# Cell.net
KiCad netlist of a schematic drawn in Altium Designer
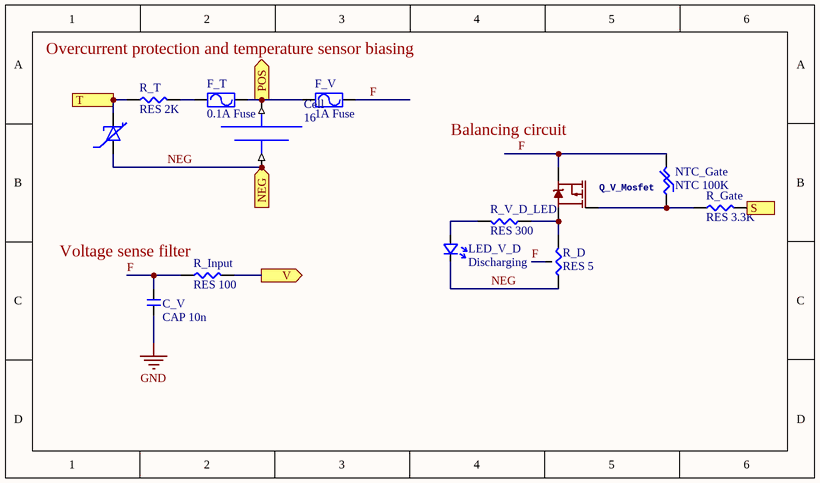
[diagram p0: Cell.SchDoc]

(export (version "E")
  (design (tool "Eeschema 10.0.6"))
  (components
    (comp (ref "Cell")
      (value "16")
      (footprint "Li1x7pVTC6T_Clips")
      (libsource (lib "ife18_TS_BMS_LTC6813_v2_Library") (part "Li1x7pVTC6T_Clip"))
    )
    (comp (ref "C_V")
      (value "CAP 10n")
      (footprint "CAP-0603")
      (description "CAP-0603")
      (libsource (lib "altium-import") (part "root_1_CAP-0603_"))
    )
    (comp (ref "F_T")
      (value "0.1A Fuse")
      (footprint "2410SMD")
      (description "0679L")
      (libsource (lib "altium-import") (part "root_0_0679L_"))
    )
    (comp (ref "F_V")
      (value "1A Fuse")
      (footprint "2410SMD")
      (description "0679L")
      (libsource (lib "altium-import") (part "root_0_0679L_"))
    )
    (comp (ref "LED_V_D")
      (value "Discharging")
      (footprint "LED-0603")
      (description "LED-0603")
      (libsource (lib "altium-import") (part "root_3_LED-0603_"))
    )
    (comp (ref "NTC_Gate")
      (value "NTC 100K")
      (footprint "NTC-0603")
      (description "NTC-0603")
      (libsource (lib "altium-import") (part "root_1_NTC-0603_"))
    )
    (comp (ref "Q_V_Mosfet")
      (value "~")
      (footprint "TO252")
      (description "DMP10H400SK3-13")
      (libsource (lib "altium-import") (part "root_0_DMP10H400SK3-13_"))
    )
    (comp (ref "R_D")
      (value "RES 5")
      (footprint "TO252-TKH-45")
      (description "TKH45")
      (libsource (lib "altium-import") (part "root_1_TKH45_"))
    )
    (comp (ref "R_Gate")
      (value "RES 3.3K")
      (footprint "RES-0603")
      (libsource (lib "altium-import") (part "root_0_RES-0603_"))
    )
    (comp (ref "R_Input")
      (value "RES 100")
      (footprint "RES-0603")
      (libsource (lib "altium-import") (part "root_0_RES-0603_"))
    )
    (comp (ref "R_T")
      (value "RES 2K")
      (footprint "RES-0603")
      (libsource (lib "altium-import") (part "root_0_RES-0603_"))
    )
    (comp (ref "R_V_D_LED")
      (value "RES 300")
      (footprint "RES-0603")
      (libsource (lib "altium-import") (part "root_2_RES-0603_"))
    )
  )
  (nets
    (net (code "1") (name "/F") (class "Default")
      (node (ref "C_V") (pin "2") (pinfunction "2_2") (pintype "passive"))
      (node (ref "F_V") (pin "1") (pinfunction "1_1") (pintype "passive"))
      (node (ref "NTC_Gate") (pin "2") (pinfunction "2_2") (pintype "passive"))
      (node (ref "Q_V_Mosfet") (pin "3") (pinfunction "S_3") (pintype "passive"))
      (node (ref "R_D") (pin "3") (pinfunction "3_3") (pintype "passive"))
      (node (ref "R_Input") (pin "1") (pinfunction "1_1") (pintype "passive"))
    )
    (net (code "2") (name "/NEG") (class "Default")
      (node (ref "Cell") (pin "-") (pinfunction "-_-") (pintype "input"))
      (node (ref "Cell") (pin "-L") (pinfunction "-L_-L") (pintype "passive"))
      (node (ref "Cell") (pin "-O") (pinfunction "-O_-O") (pintype "passive"))
      (node (ref "Cell") (pin "-R") (pinfunction "-R_-R") (pintype "passive"))
      (node (ref "Cell") (pin "T-") (pinfunction "T-_T-") (pintype "passive"))
      (node (ref "LED_V_D") (pin "K") (pinfunction "K_K") (pintype "passive"))
      (node (ref "R_D") (pin "1") (pinfunction "1_1") (pintype "passive"))
    )
    (net (code "3") (name "/POS") (class "Default")
      (node (ref "Cell") (pin "+") (pinfunction "+_+") (pintype "output"))
      (node (ref "Cell") (pin "+L") (pinfunction "+L_+L") (pintype "passive"))
      (node (ref "Cell") (pin "+O") (pinfunction "+O_+O") (pintype "passive"))
      (node (ref "Cell") (pin "+R") (pinfunction "+R_+R") (pintype "passive"))
      (node (ref "F_T") (pin "1") (pinfunction "1_1") (pintype "passive"))
      (node (ref "F_V") (pin "2") (pinfunction "2_2") (pintype "passive"))
    )
    (net (code "4") (name "/S") (class "Default")
      (node (ref "R_Gate") (pin "2") (pinfunction "2_2") (pintype "passive"))
    )
    (net (code "5") (name "/T") (class "Default")
      (node (ref "Cell") (pin "T+") (pinfunction "T+_T+") (pintype "passive"))
      (node (ref "R_T") (pin "1") (pinfunction "1_1") (pintype "passive"))
    )
    (net (code "6") (name "/V") (class "Default")
      (node (ref "R_Input") (pin "2") (pinfunction "2_2") (pintype "passive"))
    )
    (net (code "7") (name "GND") (class "Default")
      (node (ref "C_V") (pin "1") (pinfunction "1_1") (pintype "passive"))
    )
    (net (code "8") (name "Net-(F_T-Pad2)") (class "Default")
      (node (ref "F_T") (pin "2") (pinfunction "2_2") (pintype "passive"))
      (node (ref "R_T") (pin "2") (pinfunction "2_2") (pintype "passive"))
    )
    (net (code "9") (name "Net-(LED_V_D-PadA)") (class "Default")
      (node (ref "LED_V_D") (pin "A") (pinfunction "A_A") (pintype "passive"))
      (node (ref "R_V_D_LED") (pin "2") (pinfunction "2_2") (pintype "passive"))
    )
    (net (code "10") (name "Net-(Q_V_Mosfet-D)") (class "Default")
      (node (ref "Q_V_Mosfet") (pin "2") (pinfunction "D_2") (pintype "passive"))
      (node (ref "R_D") (pin "2") (pinfunction "2_2") (pintype "passive"))
      (node (ref "R_V_D_LED") (pin "1") (pinfunction "1_1") (pintype "passive"))
    )
    (net (code "11") (name "Net-(Q_V_Mosfet-G)") (class "Default")
      (node (ref "NTC_Gate") (pin "1") (pinfunction "1_1") (pintype "passive"))
      (node (ref "Q_V_Mosfet") (pin "1") (pinfunction "G_1") (pintype "passive"))
      (node (ref "R_Gate") (pin "1") (pinfunction "1_1") (pintype "passive"))
    )
  )
)
